# BBB_Connections.net
KiCad netlist of a schematic drawn in Altium Designer
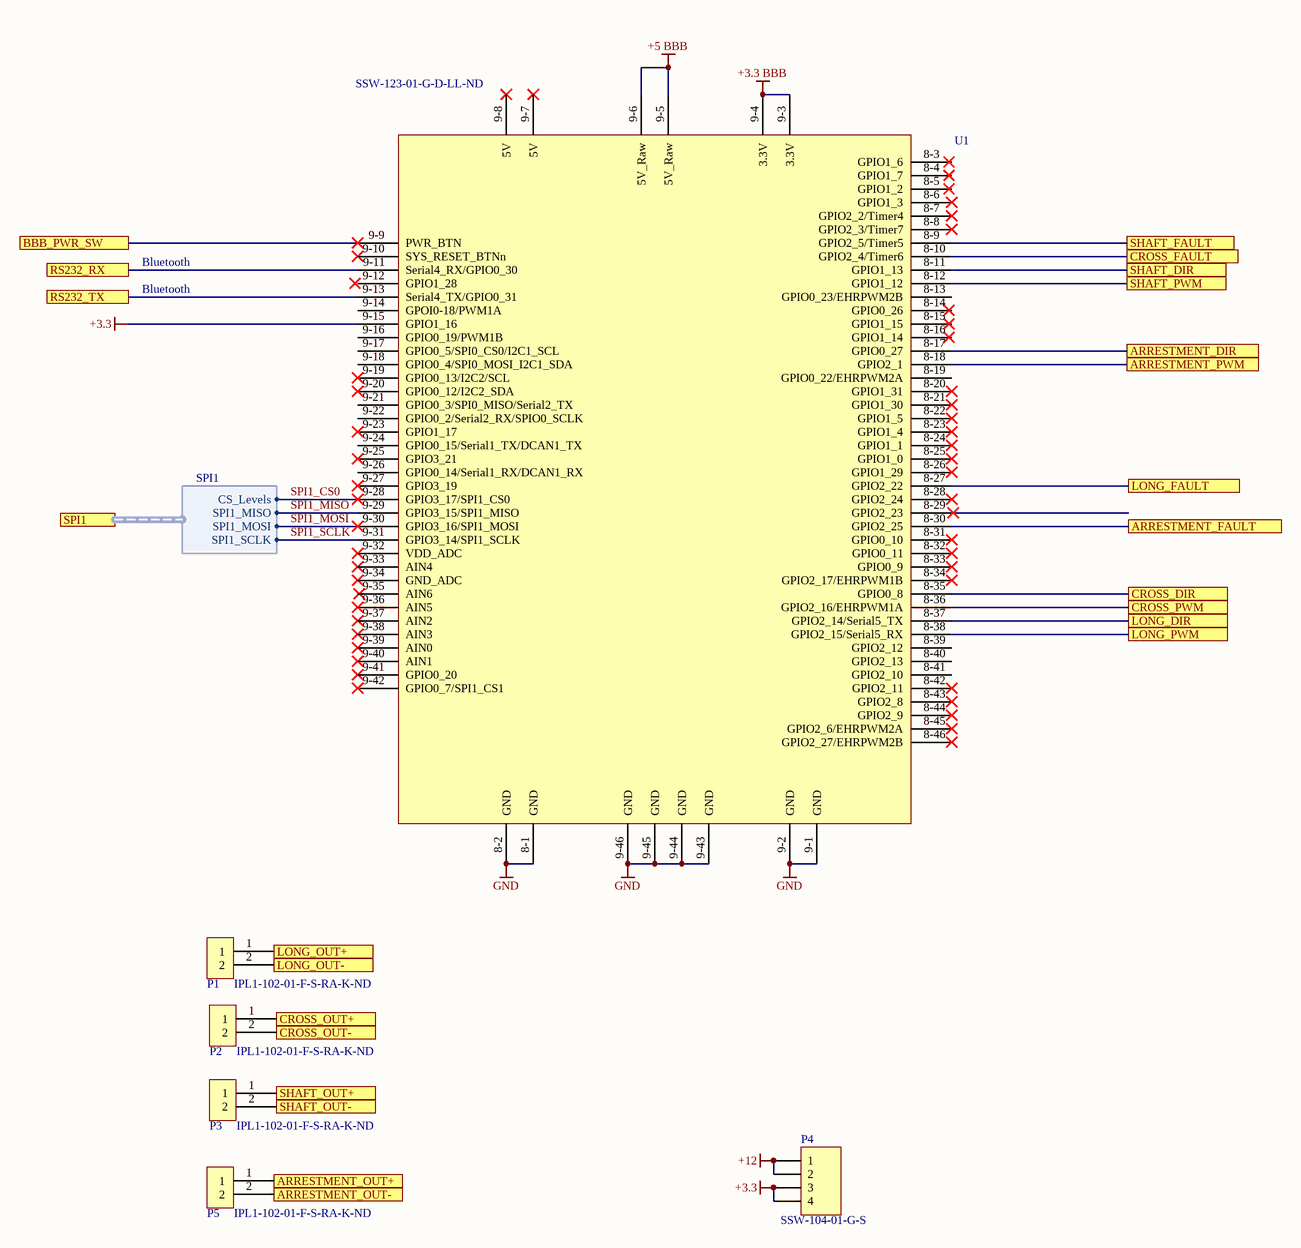
[diagram p0: BBB_Connections.SchDoc]

(export (version "E")
  (design (tool "Eeschema 10.0.6"))
  (components
    (comp (ref "P1")
      (value "IPL1-102-01-F-S-RA-K")
      (footprint "IPL1-102-01-F-S-RA-K")
      (fields
        (field (name "SUPPLIER PART NUMBER 1") "IPL1-102-01-F-S-RA-K-ND")
        (field (name "MANUFACTURER") "Samtec Inc.")
      )
      (libsource (lib "ZLS_Schematic_lib") (part "IPL1-102-01-F-S-RA-K"))
    )
    (comp (ref "P2")
      (value "IPL1-102-01-F-S-RA-K")
      (footprint "IPL1-102-01-F-S-RA-K")
      (fields
        (field (name "SUPPLIER PART NUMBER 1") "IPL1-102-01-F-S-RA-K-ND")
        (field (name "MANUFACTURER") "Samtec Inc.")
      )
      (libsource (lib "ZLS_Schematic_lib") (part "IPL1-102-01-F-S-RA-K"))
    )
    (comp (ref "P3")
      (value "IPL1-102-01-F-S-RA-K")
      (footprint "IPL1-102-01-F-S-RA-K")
      (fields
        (field (name "SUPPLIER PART NUMBER 1") "IPL1-102-01-F-S-RA-K-ND")
        (field (name "MANUFACTURER") "Samtec Inc.")
      )
      (libsource (lib "ZLS_Schematic_lib") (part "IPL1-102-01-F-S-RA-K"))
    )
    (comp (ref "P4")
      (value "SSW-104-01-G-S")
      (footprint "HDR1X4")
      (description "Header, 4-Pin")
      (fields (field (name "MANUFACTURER") "Samtec Inc."))
      (libsource (lib "Miscellaneous Connectors") (part "Header 4"))
    )
    (comp (ref "P5")
      (value "IPL1-102-01-F-S-RA-K")
      (footprint "IPL1-102-01-F-S-RA-K")
      (fields
        (field (name "SUPPLIER PART NUMBER 1") "IPL1-102-01-F-S-RA-K-ND")
        (field (name "MANUFACTURER") "Samtec Inc.")
      )
      (libsource (lib "ZLS_Schematic_lib") (part "IPL1-102-01-F-S-RA-K"))
    )
    (comp (ref "U1")
      (value "BBB")
      (footprint "Beaglebone Black Mezanine")
      (description "Beaglebone Black")
      (fields
        (field (name "SUPPLIER PART NUMBER 1") "SSW-123-01-G-D-LL-ND")
        (field (name "MANUFACTURER") "Samtec Inc.")
        (field (name "MANUFACTURER PART NUMBER") "SSW-123-01-G-D-LL")
      )
      (libsource (lib "ZLS_Schematic_lib") (part "Beaglebone_Black_Mezanine"))
    )
  )
  (nets
    (net (code "2") (name "+3.3") (class "Default")
      (node (ref "P4") (pin "3") (pinfunction "3_3") (pintype "passive"))
      (node (ref "P4") (pin "4") (pinfunction "4_4") (pintype "passive"))
      (node (ref "U1") (pin "9-15") (pinfunction "GPIO1_16_9-15") (pintype "passive"))
    )
    (net (code "3") (name "+3.3 BBB") (class "Default")
      (node (ref "U1") (pin "9-3") (pinfunction "3.3V_9-3") (pintype "passive"))
      (node (ref "U1") (pin "9-4") (pinfunction "3.3V_9-4") (pintype "passive"))
    )
    (net (code "4") (name "+5 BBB") (class "Default")
      (node (ref "U1") (pin "9-5") (pinfunction "5V_Raw_9-5") (pintype "passive"))
      (node (ref "U1") (pin "9-6") (pinfunction "5V_Raw_9-6") (pintype "passive"))
    )
    (net (code "5") (name "+12") (class "Default")
      (node (ref "P4") (pin "1") (pinfunction "1_1") (pintype "passive"))
      (node (ref "P4") (pin "2") (pinfunction "2_2") (pintype "passive"))
    )
    (net (code "6") (name "/ARRESTMENT_DIR") (class "Default")
      (node (ref "U1") (pin "8-17") (pinfunction "GPIO0_27_8-17") (pintype "passive"))
    )
    (net (code "7") (name "/ARRESTMENT_FAULT") (class "Default")
      (node (ref "U1") (pin "8-30") (pinfunction "GPIO2_25_8-30") (pintype "passive"))
    )
    (net (code "8") (name "/ARRESTMENT_OUT+") (class "Default")
      (node (ref "P5") (pin "1") (pinfunction "1_1") (pintype "passive"))
    )
    (net (code "9") (name "/ARRESTMENT_OUT-") (class "Default")
      (node (ref "P5") (pin "2") (pinfunction "2_2") (pintype "passive"))
    )
    (net (code "10") (name "/ARRESTMENT_PWM") (class "Default")
      (node (ref "U1") (pin "8-18") (pinfunction "GPIO2_1_8-18") (pintype "passive"))
    )
    (net (code "11") (name "/BBB_PWR_SW") (class "Default")
      (node (ref "U1") (pin "9-9") (pinfunction "PWR_BTN_9-9") (pintype "passive+no_connect"))
    )
    (net (code "12") (name "/CROSS_DIR") (class "Default")
      (node (ref "U1") (pin "8-35") (pinfunction "GPIO0_8_8-35") (pintype "passive"))
    )
    (net (code "13") (name "/CROSS_FAULT") (class "Default")
      (node (ref "U1") (pin "8-10") (pinfunction "GPIO2_4/Timer6_8-10") (pintype "passive"))
    )
    (net (code "14") (name "/CROSS_OUT+") (class "Default")
      (node (ref "P2") (pin "1") (pinfunction "1_1") (pintype "passive"))
    )
    (net (code "15") (name "/CROSS_OUT-") (class "Default")
      (node (ref "P2") (pin "2") (pinfunction "2_2") (pintype "passive"))
    )
    (net (code "16") (name "/CROSS_PWM") (class "Default")
      (node (ref "U1") (pin "8-36") (pinfunction "GPIO2_16/EHRPWM1A_8-36") (pintype "passive"))
    )
    (net (code "17") (name "/LONG_DIR") (class "Default")
      (node (ref "U1") (pin "8-37") (pinfunction "GPIO2_14/Serial5_TX_8-37") (pintype "passive"))
    )
    (net (code "18") (name "/LONG_FAULT") (class "Default")
      (node (ref "U1") (pin "8-27") (pinfunction "GPIO2_22_8-27") (pintype "passive"))
    )
    (net (code "19") (name "/LONG_OUT+") (class "Default")
      (node (ref "P1") (pin "1") (pinfunction "1_1") (pintype "passive"))
    )
    (net (code "20") (name "/LONG_OUT-") (class "Default")
      (node (ref "P1") (pin "2") (pinfunction "2_2") (pintype "passive"))
    )
    (net (code "21") (name "/LONG_PWM") (class "Default")
      (node (ref "U1") (pin "8-38") (pinfunction "GPIO2_15/Serial5_RX_8-38") (pintype "passive"))
    )
    (net (code "22") (name "/RS232_RX") (class "Default")
      (node (ref "U1") (pin "9-11") (pinfunction "Serial4_RX/GPIO0_30_9-11") (pintype "passive"))
    )
    (net (code "23") (name "/RS232_TX") (class "Default")
      (node (ref "U1") (pin "9-13") (pinfunction "Serial4_TX/GPIO0_31_9-13") (pintype "passive"))
    )
    (net (code "24") (name "/SHAFT_DIR") (class "Default")
      (node (ref "U1") (pin "8-11") (pinfunction "GPIO1_13_8-11") (pintype "passive"))
    )
    (net (code "25") (name "/SHAFT_FAULT") (class "Default")
      (node (ref "U1") (pin "8-9") (pinfunction "GPIO2_5/Timer5_8-9") (pintype "passive"))
    )
    (net (code "26") (name "/SHAFT_OUT+") (class "Default")
      (node (ref "P3") (pin "1") (pinfunction "1_1") (pintype "passive"))
    )
    (net (code "27") (name "/SHAFT_OUT-") (class "Default")
      (node (ref "P3") (pin "2") (pinfunction "2_2") (pintype "passive"))
    )
    (net (code "28") (name "/SHAFT_PWM") (class "Default")
      (node (ref "U1") (pin "8-12") (pinfunction "GPIO1_12_8-12") (pintype "passive"))
    )
    (net (code "29") (name "/SPI1_CS0") (class "Default")
      (node (ref "U1") (pin "9-28") (pinfunction "GPIO3_17/SPI1_CS0_9-28") (pintype "passive+no_connect"))
    )
    (net (code "30") (name "/SPI1_MISO") (class "Default")
      (node (ref "U1") (pin "9-29") (pinfunction "GPIO3_15/SPI1_MISO_9-29") (pintype "passive"))
    )
    (net (code "31") (name "/SPI1_MOSI") (class "Default")
      (node (ref "U1") (pin "9-30") (pinfunction "GPIO3_16/SPI1_MOSI_9-30") (pintype "passive+no_connect"))
    )
    (net (code "32") (name "/SPI1_SCLK") (class "Default")
      (node (ref "U1") (pin "9-31") (pinfunction "GPIO3_14/SPI1_SCLK_9-31") (pintype "passive"))
    )
    (net (code "34") (name "GND") (class "Default")
      (node (ref "U1") (pin "8-1") (pinfunction "GND_8-1") (pintype "passive"))
      (node (ref "U1") (pin "8-2") (pinfunction "GND_8-2") (pintype "passive"))
      (node (ref "U1") (pin "9-1") (pinfunction "GND_9-1") (pintype "passive"))
      (node (ref "U1") (pin "9-2") (pinfunction "GND_9-2") (pintype "passive"))
      (node (ref "U1") (pin "9-43") (pinfunction "GND_9-43") (pintype "passive"))
      (node (ref "U1") (pin "9-44") (pinfunction "GND_9-44") (pintype "passive"))
      (node (ref "U1") (pin "9-45") (pinfunction "GND_9-45") (pintype "passive"))
      (node (ref "U1") (pin "9-46") (pinfunction "GND_9-46") (pintype "passive"))
    )
    (net (code "35") (name "unconnected-(U1-5V-Pad9-7)") (class "Default")
      (node (ref "U1") (pin "9-7") (pinfunction "5V_9-7") (pintype "passive+no_connect"))
    )
    (net (code "36") (name "unconnected-(U1-5V-Pad9-8)") (class "Default")
      (node (ref "U1") (pin "9-8") (pinfunction "5V_9-8") (pintype "passive+no_connect"))
    )
    (net (code "37") (name "unconnected-(U1-AIN0-Pad9-39)") (class "Default")
      (node (ref "U1") (pin "9-39") (pinfunction "AIN0_9-39") (pintype "passive+no_connect"))
    )
    (net (code "38") (name "unconnected-(U1-AIN1-Pad9-40)") (class "Default")
      (node (ref "U1") (pin "9-40") (pinfunction "AIN1_9-40") (pintype "passive+no_connect"))
    )
    (net (code "39") (name "unconnected-(U1-AIN2-Pad9-37)") (class "Default")
      (node (ref "U1") (pin "9-37") (pinfunction "AIN2_9-37") (pintype "passive+no_connect"))
    )
    (net (code "40") (name "unconnected-(U1-AIN3-Pad9-38)") (class "Default")
      (node (ref "U1") (pin "9-38") (pinfunction "AIN3_9-38") (pintype "passive+no_connect"))
    )
    (net (code "41") (name "unconnected-(U1-AIN4-Pad9-33)") (class "Default")
      (node (ref "U1") (pin "9-33") (pinfunction "AIN4_9-33") (pintype "passive+no_connect"))
    )
    (net (code "42") (name "unconnected-(U1-AIN5-Pad9-36)") (class "Default")
      (node (ref "U1") (pin "9-36") (pinfunction "AIN5_9-36") (pintype "passive+no_connect"))
    )
    (net (code "43") (name "unconnected-(U1-AIN6-Pad9-35)") (class "Default")
      (node (ref "U1") (pin "9-35") (pinfunction "AIN6_9-35") (pintype "passive"))
    )
    (net (code "44") (name "unconnected-(U1-GND_ADC-Pad9-34)") (class "Default")
      (node (ref "U1") (pin "9-34") (pinfunction "GND_ADC_9-34") (pintype "passive+no_connect"))
    )
    (net (code "45") (name "unconnected-(U1-GPIO0_2{slash}Serial2_RX{slash}SPIO0_SCLK-Pad9-22)") (class "Default")
      (node (ref "U1") (pin "9-22") (pinfunction "GPIO0_2/Serial2_RX/SPIO0_SCLK_9-22") (pintype "passive"))
    )
    (net (code "46") (name "unconnected-(U1-GPIO0_3{slash}SPI0_MISO{slash}Serial2_TX-Pad9-21)") (class "Default")
      (node (ref "U1") (pin "9-21") (pinfunction "GPIO0_3/SPI0_MISO/Serial2_TX_9-21") (pintype "passive"))
    )
    (net (code "47") (name "unconnected-(U1-GPIO0_4{slash}SPI0_MOSI_I2C1_SDA-Pad9-18)") (class "Default")
      (node (ref "U1") (pin "9-18") (pinfunction "GPIO0_4/SPI0_MOSI_I2C1_SDA_9-18") (pintype "passive"))
    )
    (net (code "48") (name "unconnected-(U1-GPIO0_5{slash}SPI0_CS0{slash}I2C1_SCL-Pad9-17)") (class "Default")
      (node (ref "U1") (pin "9-17") (pinfunction "GPIO0_5/SPI0_CS0/I2C1_SCL_9-17") (pintype "passive"))
    )
    (net (code "49") (name "unconnected-(U1-GPIO0_7{slash}SPI1_CS1-Pad9-42)") (class "Default")
      (node (ref "U1") (pin "9-42") (pinfunction "GPIO0_7/SPI1_CS1_9-42") (pintype "passive+no_connect"))
    )
    (net (code "50") (name "unconnected-(U1-GPIO0_9-Pad8-33)") (class "Default")
      (node (ref "U1") (pin "8-33") (pinfunction "GPIO0_9_8-33") (pintype "passive+no_connect"))
    )
    (net (code "51") (name "unconnected-(U1-GPIO0_10-Pad8-31)") (class "Default")
      (node (ref "U1") (pin "8-31") (pinfunction "GPIO0_10_8-31") (pintype "passive+no_connect"))
    )
    (net (code "52") (name "unconnected-(U1-GPIO0_11-Pad8-32)") (class "Default")
      (node (ref "U1") (pin "8-32") (pinfunction "GPIO0_11_8-32") (pintype "passive+no_connect"))
    )
    (net (code "53") (name "unconnected-(U1-GPIO0_12{slash}I2C2_SDA-Pad9-20)") (class "Default")
      (node (ref "U1") (pin "9-20") (pinfunction "GPIO0_12/I2C2_SDA_9-20") (pintype "passive+no_connect"))
    )
    (net (code "54") (name "unconnected-(U1-GPIO0_13{slash}I2C2{slash}SCL-Pad9-19)") (class "Default")
      (node (ref "U1") (pin "9-19") (pinfunction "GPIO0_13/I2C2/SCL_9-19") (pintype "passive+no_connect"))
    )
    (net (code "55") (name "unconnected-(U1-GPIO0_14{slash}Serial1_RX{slash}DCAN1_RX-Pad9-26)") (class "Default")
      (node (ref "U1") (pin "9-26") (pinfunction "GPIO0_14/Serial1_RX/DCAN1_RX_9-26") (pintype "passive"))
    )
    (net (code "56") (name "unconnected-(U1-GPIO0_15{slash}Serial1_TX{slash}DCAN1_TX-Pad9-24)") (class "Default")
      (node (ref "U1") (pin "9-24") (pinfunction "GPIO0_15/Serial1_TX/DCAN1_TX_9-24") (pintype "passive"))
    )
    (net (code "57") (name "unconnected-(U1-GPIO0_19{slash}PWM1B-Pad9-16)") (class "Default")
      (node (ref "U1") (pin "9-16") (pinfunction "GPIO0_19/PWM1B_9-16") (pintype "passive"))
    )
    (net (code "58") (name "unconnected-(U1-GPIO0_20-Pad9-41)") (class "Default")
      (node (ref "U1") (pin "9-41") (pinfunction "GPIO0_20_9-41") (pintype "passive+no_connect"))
    )
    (net (code "59") (name "unconnected-(U1-GPIO0_22{slash}EHRPWM2A-Pad8-19)") (class "Default")
      (node (ref "U1") (pin "8-19") (pinfunction "GPIO0_22/EHRPWM2A_8-19") (pintype "passive"))
    )
    (net (code "60") (name "unconnected-(U1-GPIO0_23{slash}EHRPWM2B-Pad8-13)") (class "Default")
      (node (ref "U1") (pin "8-13") (pinfunction "GPIO0_23/EHRPWM2B_8-13") (pintype "passive"))
    )
    (net (code "61") (name "unconnected-(U1-GPIO0_26-Pad8-14)") (class "Default")
      (node (ref "U1") (pin "8-14") (pinfunction "GPIO0_26_8-14") (pintype "passive"))
    )
    (net (code "62") (name "unconnected-(U1-GPIO1_0-Pad8-25)") (class "Default")
      (node (ref "U1") (pin "8-25") (pinfunction "GPIO1_0_8-25") (pintype "passive+no_connect"))
    )
    (net (code "63") (name "unconnected-(U1-GPIO1_1-Pad8-24)") (class "Default")
      (node (ref "U1") (pin "8-24") (pinfunction "GPIO1_1_8-24") (pintype "passive+no_connect"))
    )
    (net (code "64") (name "unconnected-(U1-GPIO1_2-Pad8-5)") (class "Default")
      (node (ref "U1") (pin "8-5") (pinfunction "GPIO1_2_8-5") (pintype "passive"))
    )
    (net (code "65") (name "unconnected-(U1-GPIO1_3-Pad8-6)") (class "Default")
      (node (ref "U1") (pin "8-6") (pinfunction "GPIO1_3_8-6") (pintype "passive+no_connect"))
    )
    (net (code "66") (name "unconnected-(U1-GPIO1_4-Pad8-23)") (class "Default")
      (node (ref "U1") (pin "8-23") (pinfunction "GPIO1_4_8-23") (pintype "passive+no_connect"))
    )
    (net (code "67") (name "unconnected-(U1-GPIO1_5-Pad8-22)") (class "Default")
      (node (ref "U1") (pin "8-22") (pinfunction "GPIO1_5_8-22") (pintype "passive+no_connect"))
    )
    (net (code "68") (name "unconnected-(U1-GPIO1_6-Pad8-3)") (class "Default")
      (node (ref "U1") (pin "8-3") (pinfunction "GPIO1_6_8-3") (pintype "passive"))
    )
    (net (code "69") (name "unconnected-(U1-GPIO1_7-Pad8-4)") (class "Default")
      (node (ref "U1") (pin "8-4") (pinfunction "GPIO1_7_8-4") (pintype "passive"))
    )
    (net (code "70") (name "unconnected-(U1-GPIO1_14-Pad8-16)") (class "Default")
      (node (ref "U1") (pin "8-16") (pinfunction "GPIO1_14_8-16") (pintype "passive"))
    )
    (net (code "71") (name "unconnected-(U1-GPIO1_15-Pad8-15)") (class "Default")
      (node (ref "U1") (pin "8-15") (pinfunction "GPIO1_15_8-15") (pintype "passive"))
    )
    (net (code "72") (name "unconnected-(U1-GPIO1_17-Pad9-23)") (class "Default")
      (node (ref "U1") (pin "9-23") (pinfunction "GPIO1_17_9-23") (pintype "passive+no_connect"))
    )
    (net (code "73") (name "unconnected-(U1-GPIO1_28-Pad9-12)") (class "Default")
      (node (ref "U1") (pin "9-12") (pinfunction "GPIO1_28_9-12") (pintype "passive"))
    )
    (net (code "74") (name "unconnected-(U1-GPIO1_29-Pad8-26)") (class "Default")
      (node (ref "U1") (pin "8-26") (pinfunction "GPIO1_29_8-26") (pintype "passive+no_connect"))
    )
    (net (code "75") (name "unconnected-(U1-GPIO1_30-Pad8-21)") (class "Default")
      (node (ref "U1") (pin "8-21") (pinfunction "GPIO1_30_8-21") (pintype "passive+no_connect"))
    )
    (net (code "76") (name "unconnected-(U1-GPIO1_31-Pad8-20)") (class "Default")
      (node (ref "U1") (pin "8-20") (pinfunction "GPIO1_31_8-20") (pintype "passive+no_connect"))
    )
    (net (code "77") (name "unconnected-(U1-GPIO2_2{slash}Timer4-Pad8-7)") (class "Default")
      (node (ref "U1") (pin "8-7") (pinfunction "GPIO2_2/Timer4_8-7") (pintype "passive+no_connect"))
    )
    (net (code "78") (name "unconnected-(U1-GPIO2_3{slash}Timer7-Pad8-8)") (class "Default")
      (node (ref "U1") (pin "8-8") (pinfunction "GPIO2_3/Timer7_8-8") (pintype "passive+no_connect"))
    )
    (net (code "79") (name "unconnected-(U1-GPIO2_6{slash}EHRPWM2A-Pad8-45)") (class "Default")
      (node (ref "U1") (pin "8-45") (pinfunction "GPIO2_6/EHRPWM2A_8-45") (pintype "passive+no_connect"))
    )
    (net (code "80") (name "unconnected-(U1-GPIO2_8-Pad8-43)") (class "Default")
      (node (ref "U1") (pin "8-43") (pinfunction "GPIO2_8_8-43") (pintype "passive+no_connect"))
    )
    (net (code "81") (name "unconnected-(U1-GPIO2_9-Pad8-44)") (class "Default")
      (node (ref "U1") (pin "8-44") (pinfunction "GPIO2_9_8-44") (pintype "passive+no_connect"))
    )
    (net (code "82") (name "unconnected-(U1-GPIO2_10-Pad8-41)") (class "Default")
      (node (ref "U1") (pin "8-41") (pinfunction "GPIO2_10_8-41") (pintype "passive"))
    )
    (net (code "83") (name "unconnected-(U1-GPIO2_11-Pad8-42)") (class "Default")
      (node (ref "U1") (pin "8-42") (pinfunction "GPIO2_11_8-42") (pintype "passive+no_connect"))
    )
    (net (code "84") (name "unconnected-(U1-GPIO2_12-Pad8-39)") (class "Default")
      (node (ref "U1") (pin "8-39") (pinfunction "GPIO2_12_8-39") (pintype "passive"))
    )
    (net (code "85") (name "unconnected-(U1-GPIO2_13-Pad8-40)") (class "Default")
      (node (ref "U1") (pin "8-40") (pinfunction "GPIO2_13_8-40") (pintype "passive"))
    )
    (net (code "86") (name "unconnected-(U1-GPIO2_17{slash}EHRPWM1B-Pad8-34)") (class "Default")
      (node (ref "U1") (pin "8-34") (pinfunction "GPIO2_17/EHRPWM1B_8-34") (pintype "passive+no_connect"))
    )
    (net (code "87") (name "unconnected-(U1-GPIO2_23-Pad8-29)") (class "Default")
      (node (ref "U1") (pin "8-29") (pinfunction "GPIO2_23_8-29") (pintype "passive"))
    )
    (net (code "88") (name "unconnected-(U1-GPIO2_24-Pad8-28)") (class "Default")
      (node (ref "U1") (pin "8-28") (pinfunction "GPIO2_24_8-28") (pintype "passive+no_connect"))
    )
    (net (code "89") (name "unconnected-(U1-GPIO2_27{slash}EHRPWM2B-Pad8-46)") (class "Default")
      (node (ref "U1") (pin "8-46") (pinfunction "GPIO2_27/EHRPWM2B_8-46") (pintype "passive+no_connect"))
    )
    (net (code "90") (name "unconnected-(U1-GPIO3_19-Pad9-27)") (class "Default")
      (node (ref "U1") (pin "9-27") (pinfunction "GPIO3_19_9-27") (pintype "passive+no_connect"))
    )
    (net (code "91") (name "unconnected-(U1-GPIO3_21-Pad9-25)") (class "Default")
      (node (ref "U1") (pin "9-25") (pinfunction "GPIO3_21_9-25") (pintype "passive+no_connect"))
    )
    (net (code "92") (name "unconnected-(U1-GPOI0-18{slash}PWM1A-Pad9-14)") (class "Default")
      (node (ref "U1") (pin "9-14") (pinfunction "GPOI0-18/PWM1A_9-14") (pintype "passive"))
    )
    (net (code "93") (name "unconnected-(U1-SYS_RESET_BTNn-Pad9-10)") (class "Default")
      (node (ref "U1") (pin "9-10") (pinfunction "SYS_RESET_BTNn_9-10") (pintype "passive+no_connect"))
    )
    (net (code "94") (name "unconnected-(U1-VDD_ADC-Pad9-32)") (class "Default")
      (node (ref "U1") (pin "9-32") (pinfunction "VDD_ADC_9-32") (pintype "passive+no_connect"))
    )
  )
)
